# AMP.net
KiCad netlist of a schematic drawn in Altium Designer
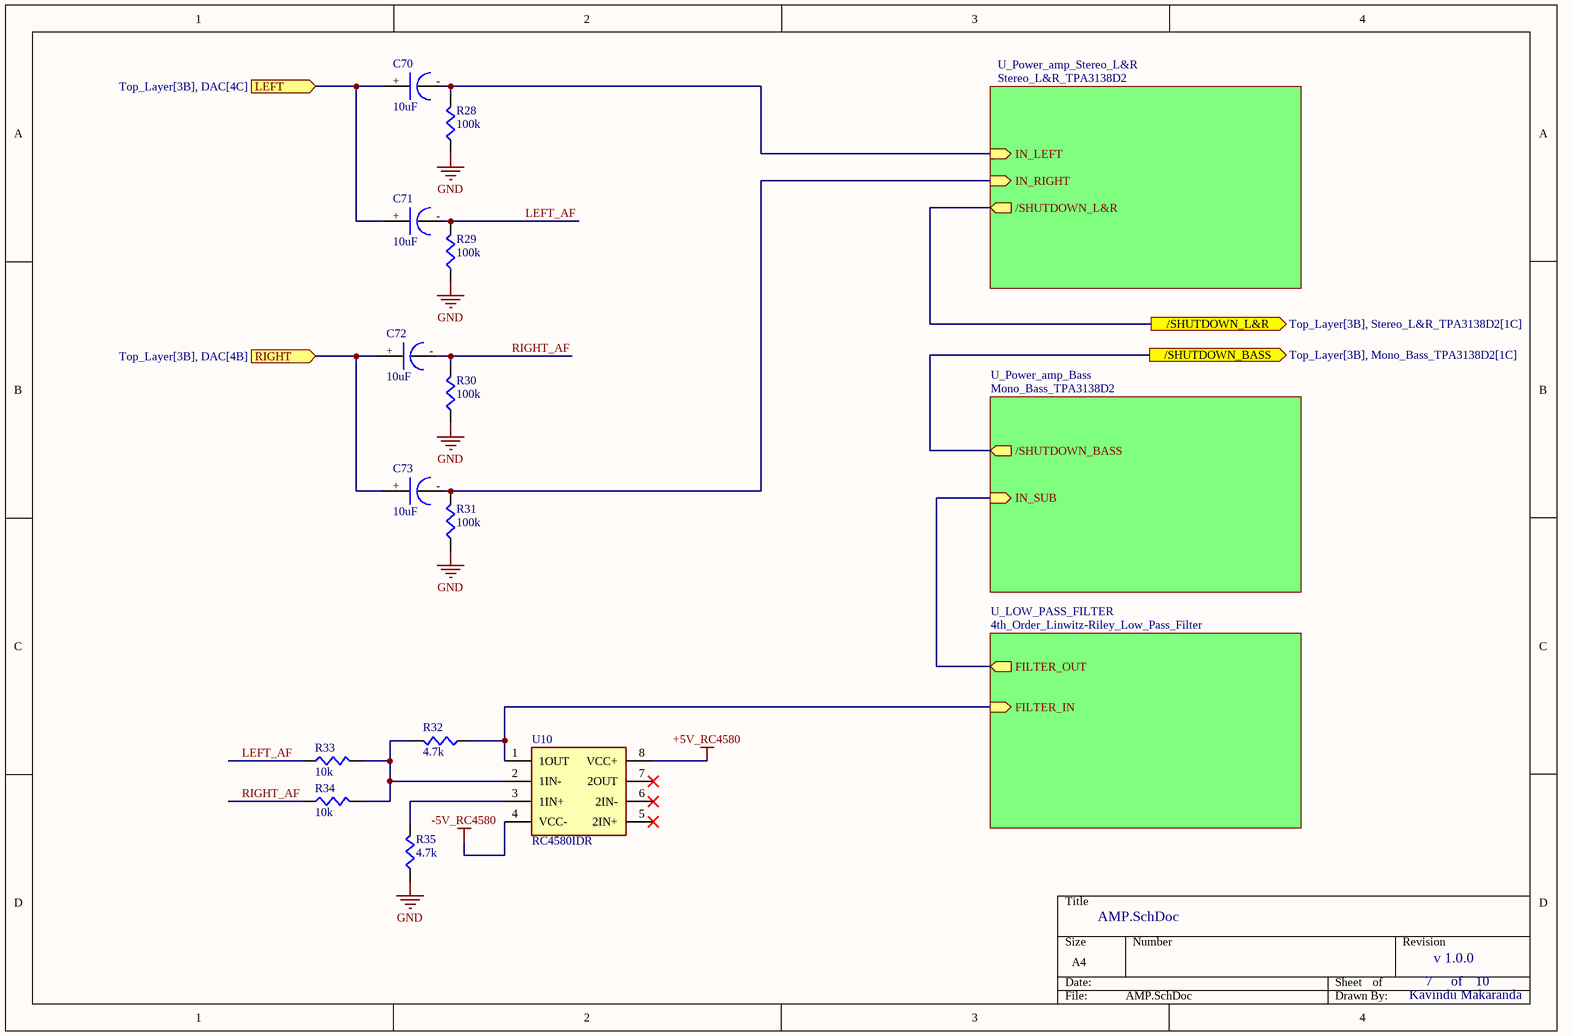
[diagram p0: AMP.SchDoc]

(export (version "E")
  (design (tool "Eeschema 10.0.6"))
  (components
    (comp (ref "C70")
      (value "10uF")
      (footprint "CAPD6.3XL5.8X61M")
      (libsource (lib "Schlib1") (part "CPD6.3XL5.8_10uF_POLYMER"))
    )
    (comp (ref "C71")
      (value "10uF")
      (footprint "CAPD6.3XL5.8X61M")
      (libsource (lib "Schlib1") (part "CPD6.3XL5.8_10uF_POLYMER"))
    )
    (comp (ref "C72")
      (value "10uF")
      (footprint "CAPD6.3XL5.8X61M")
      (libsource (lib "Schlib1") (part "CPD6.3XL5.8_10uF_POLYMER"))
    )
    (comp (ref "C73")
      (value "10uF")
      (footprint "CAPD6.3XL5.8X61M")
      (libsource (lib "Schlib1") (part "CPD6.3XL5.8_10uF_POLYMER"))
    )
    (comp (ref "R28")
      (value "100k")
      (footprint "RECS0603X45N")
      (libsource (lib "Schlib1") (part "RESC0603_100K_THIN"))
    )
    (comp (ref "R29")
      (value "100k")
      (footprint "RECS0603X45N")
      (libsource (lib "Schlib1") (part "RESC0603_100K_THIN"))
    )
    (comp (ref "R30")
      (value "100k")
      (footprint "RECS0603X45N")
      (libsource (lib "Schlib1") (part "RESC0603_100K_THIN"))
    )
    (comp (ref "R31")
      (value "100k")
      (footprint "RECS0603X45N")
      (libsource (lib "Schlib1") (part "RESC0603_100K_THIN"))
    )
    (comp (ref "R32")
      (value "4.7k")
      (footprint "RECS0603X45N")
      (libsource (lib "Schlib1") (part "RESC0603_4.7K_THIN"))
    )
    (comp (ref "R33")
      (value "10k")
      (footprint "RECS0603X45N")
      (libsource (lib "Schlib1") (part "RESC0603_10K_THIN"))
    )
    (comp (ref "R34")
      (value "10k")
      (footprint "RECS0603X45N")
      (libsource (lib "Schlib1") (part "RESC0603_10K_THIN"))
    )
    (comp (ref "R35")
      (value "4.7k")
      (footprint "RECS0603X45N")
      (libsource (lib "Schlib1") (part "RESC0603_4.7K_THIN"))
    )
    (comp (ref "U10")
      (value "RC4580IDR")
      (footprint "SOIC127P600X175-8N")
      (fields (field (name "MOUSER PART NUMBER") "595-RC4580IDR"))
      (libsource (lib "Schlib1") (part "RC4580IDR"))
    )
  )
  (nets
    (net (code "1") (name "+5V_RC4580") (class "Default")
      (node (ref "U10") (pin "8") (pinfunction "VCC+_8") (pintype "passive"))
    )
    (net (code "2") (name "-5V_RC4580") (class "Default")
      (node (ref "U10") (pin "4") (pinfunction "VCC-_4") (pintype "passive"))
    )
    (net (code "3") (name "/FILTER_IN") (class "Default")
      (node (ref "R32") (pin "1") (pinfunction "1_1") (pintype "passive"))
      (node (ref "U10") (pin "1") (pinfunction "1OUT_1") (pintype "passive"))
    )
    (net (code "5") (name "/IN_LEFT") (class "Default")
      (node (ref "C70") (pin "2") (pinfunction "2_2") (pintype "passive"))
      (node (ref "R28") (pin "2") (pinfunction "2_2") (pintype "passive"))
    )
    (net (code "6") (name "/IN_RIGHT") (class "Default")
      (node (ref "C73") (pin "2") (pinfunction "2_2") (pintype "passive"))
      (node (ref "R31") (pin "2") (pinfunction "2_2") (pintype "passive"))
    )
    (net (code "7") (name "/LEFT") (class "Default")
      (node (ref "C70") (pin "1") (pinfunction "1_1") (pintype "passive"))
      (node (ref "C71") (pin "1") (pinfunction "1_1") (pintype "passive"))
    )
    (net (code "8") (name "/LEFT_AF") (class "Default")
      (node (ref "C71") (pin "2") (pinfunction "2_2") (pintype "passive"))
      (node (ref "R29") (pin "2") (pinfunction "2_2") (pintype "passive"))
      (node (ref "R33") (pin "1") (pinfunction "1_1") (pintype "passive"))
    )
    (net (code "9") (name "/RIGHT") (class "Default")
      (node (ref "C72") (pin "1") (pinfunction "1_1") (pintype "passive"))
      (node (ref "C73") (pin "1") (pinfunction "1_1") (pintype "passive"))
    )
    (net (code "10") (name "/RIGHT_AF") (class "Default")
      (node (ref "C72") (pin "2") (pinfunction "2_2") (pintype "passive"))
      (node (ref "R30") (pin "2") (pinfunction "2_2") (pintype "passive"))
      (node (ref "R34") (pin "1") (pinfunction "1_1") (pintype "passive"))
    )
    (net (code "13") (name "GND") (class "Default")
      (node (ref "R28") (pin "1") (pinfunction "1_1") (pintype "passive"))
      (node (ref "R29") (pin "1") (pinfunction "1_1") (pintype "passive"))
      (node (ref "R30") (pin "1") (pinfunction "1_1") (pintype "passive"))
      (node (ref "R31") (pin "1") (pinfunction "1_1") (pintype "passive"))
      (node (ref "R35") (pin "1") (pinfunction "1_1") (pintype "passive"))
    )
    (net (code "14") (name "Net-(U10-1IN+)") (class "Default")
      (node (ref "R35") (pin "2") (pinfunction "2_2") (pintype "passive"))
      (node (ref "U10") (pin "3") (pinfunction "1IN+_3") (pintype "passive"))
    )
    (net (code "15") (name "Net-(U10-1IN-)") (class "Default")
      (node (ref "R32") (pin "2") (pinfunction "2_2") (pintype "passive"))
      (node (ref "R33") (pin "2") (pinfunction "2_2") (pintype "passive"))
      (node (ref "R34") (pin "2") (pinfunction "2_2") (pintype "passive"))
      (node (ref "U10") (pin "2") (pinfunction "1IN-_2") (pintype "passive"))
    )
    (net (code "16") (name "unconnected-(U10-2IN+-Pad5)") (class "Default")
      (node (ref "U10") (pin "5") (pinfunction "2IN+_5") (pintype "passive+no_connect"))
    )
    (net (code "17") (name "unconnected-(U10-2IN--Pad6)") (class "Default")
      (node (ref "U10") (pin "6") (pinfunction "2IN-_6") (pintype "passive+no_connect"))
    )
    (net (code "18") (name "unconnected-(U10-2OUT-Pad7)") (class "Default")
      (node (ref "U10") (pin "7") (pinfunction "2OUT_7") (pintype "passive+no_connect"))
    )
  )
)
